# djshield2.net
KiCad netlist of a schematic drawn in EAGLE
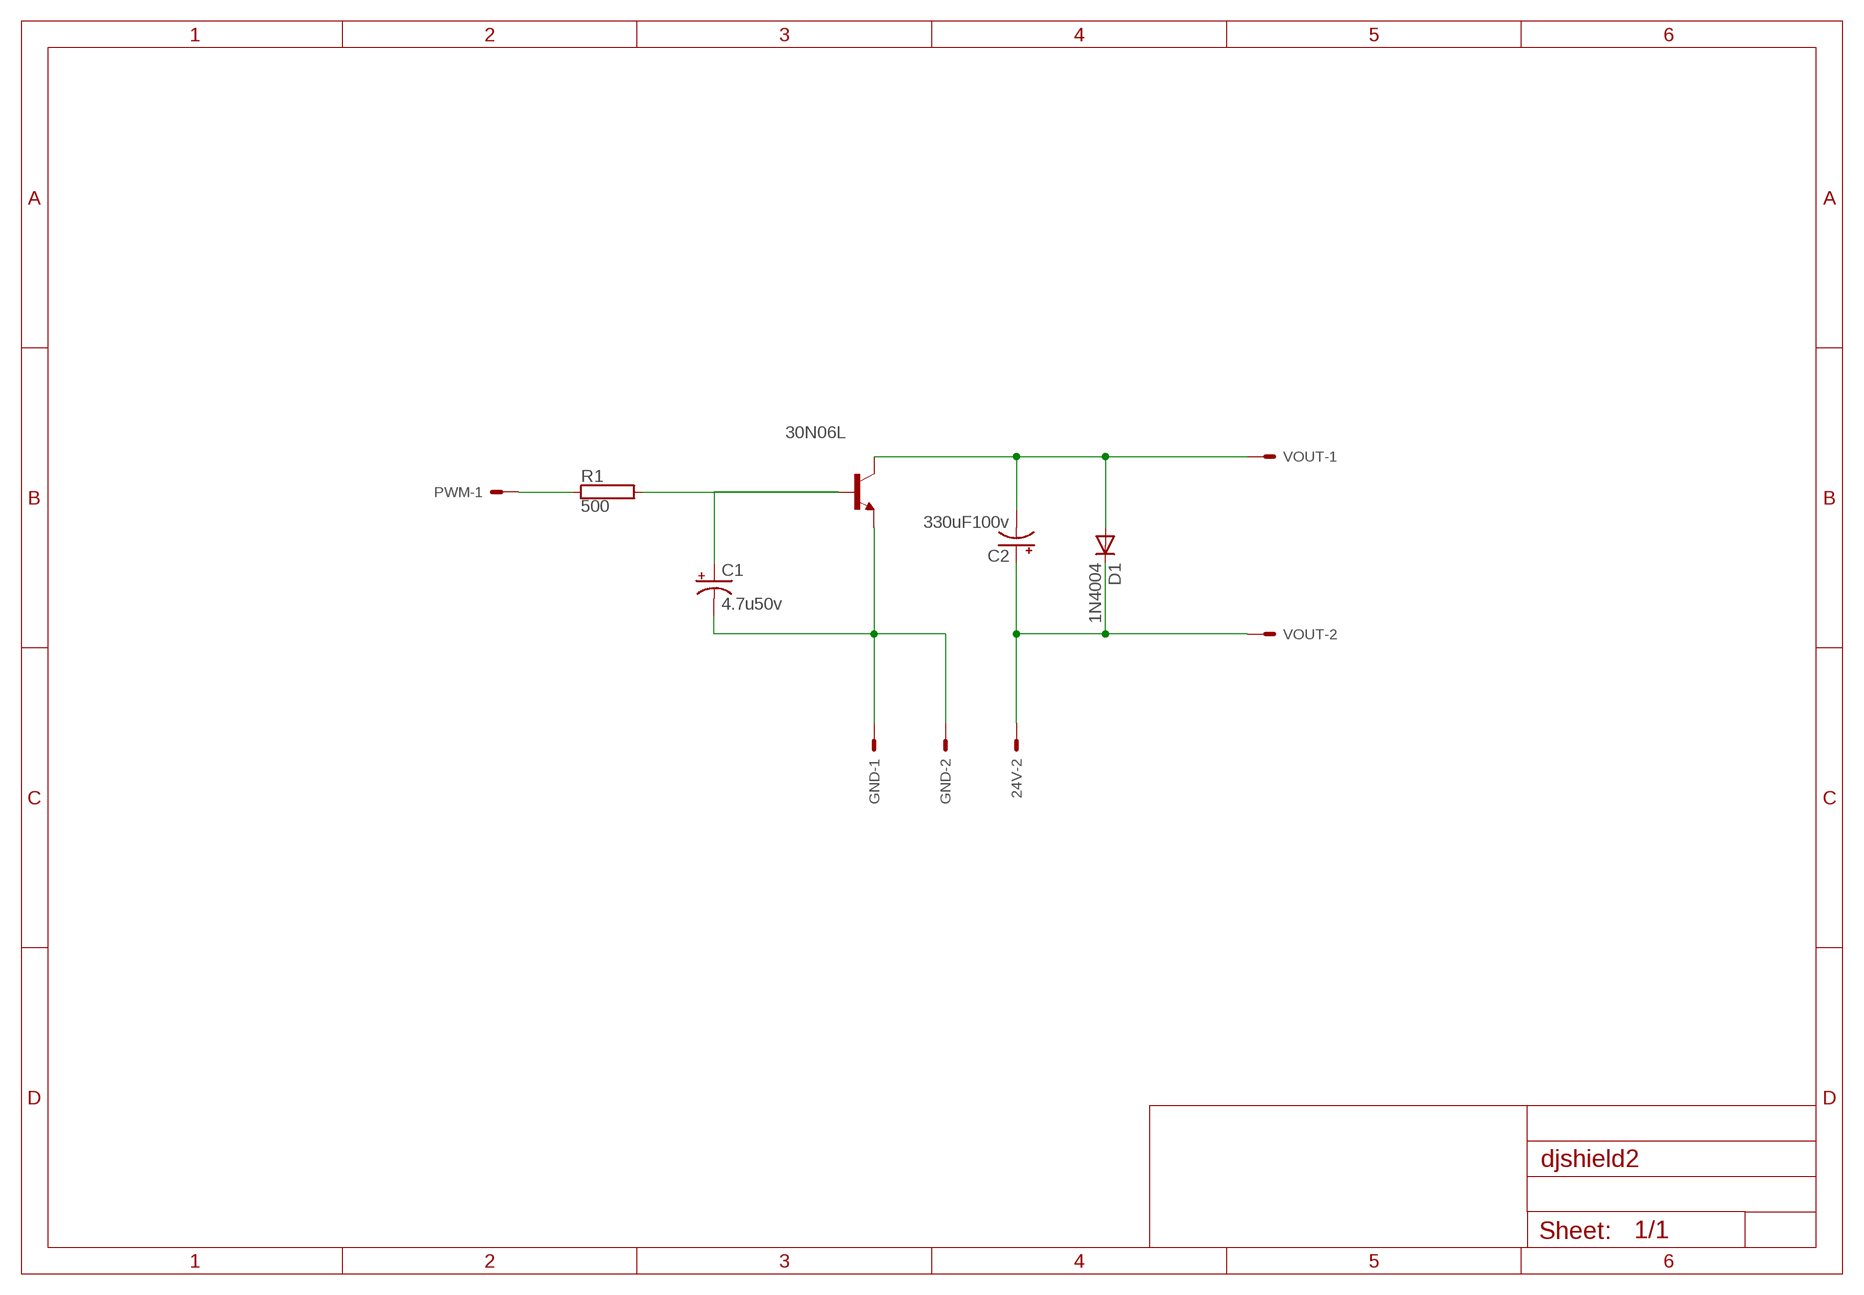
[diagram p0: schematic, sheet 1]

(export (version "E")
  (design (tool "Eeschema 10.0.6"))
  (components
    (comp (ref "24V")
      (value "87758-0216")
      (footprint "eagle-import:87758-0216")
      (libsource (lib "eagle-import") (part "87758-0216"))
    )
    (comp (ref "30N06L")
      (value "-NPN-TO126")
      (footprint "eagle-import:TO126")
      (libsource (lib "eagle-import") (part "-NPN-TO126"))
    )
    (comp (ref "C1")
      (value "4.7u50v")
      (footprint "eagle-import:E1,8-4")
      (libsource (lib "eagle-import") (part "resistor_CPOL-USE1.8-4"))
    )
    (comp (ref "C2")
      (value "330uF100v")
      (footprint "eagle-import:E35-18")
      (libsource (lib "eagle-import") (part "CPOL-USE35-18AXIAL"))
    )
    (comp (ref "D1")
      (value "1N4004")
      (footprint "eagle-import:DO41-10")
      (libsource (lib "eagle-import") (part "1N4004"))
    )
    (comp (ref "GND")
      (value "87758-0216")
      (footprint "eagle-import:87758-0216")
      (libsource (lib "eagle-import") (part "87758-0216"))
    )
    (comp (ref "PWM")
      (value "87758-0216")
      (footprint "eagle-import:87758-0216")
      (libsource (lib "eagle-import") (part "87758-0216"))
    )
    (comp (ref "R1")
      (value "500")
      (footprint "eagle-import:RS1_4")
      (fields (field (name "MF") "OHMITE") (field (name "MPN") "RRS1K0"))
      (libsource (lib "eagle-import") (part "RRS1/4"))
    )
    (comp (ref "VOUT")
      (value "87758-0216")
      (footprint "eagle-import:87758-0216")
      (libsource (lib "eagle-import") (part "87758-0216"))
    )
  )
  (nets
    (net (code "1") (name "Net-(24VB-S)") (class "Default")
      (node (ref "24V") (pin "2") (pinfunction "S_2") (pintype "passive"))
      (node (ref "C2") (pin "+") (pinfunction "+_+") (pintype "passive"))
      (node (ref "D1") (pin "C") (pinfunction "C_C") (pintype "passive"))
      (node (ref "VOUT") (pin "2") (pinfunction "S_2") (pintype "passive"))
    )
    (net (code "2") (name "Net-(30N06L-B)") (class "Default")
      (node (ref "30N06L") (pin "3") (pinfunction "B_3") (pintype "passive"))
      (node (ref "C1") (pin "+") (pinfunction "+_+") (pintype "passive"))
      (node (ref "R1") (pin "2") (pinfunction "2_2") (pintype "passive"))
    )
    (net (code "3") (name "Net-(30N06L-C)") (class "Default")
      (node (ref "30N06L") (pin "2") (pinfunction "C_2") (pintype "passive"))
      (node (ref "C2") (pin "-") (pinfunction "-_-") (pintype "passive"))
      (node (ref "D1") (pin "A") (pinfunction "A_A") (pintype "passive"))
      (node (ref "VOUT") (pin "1") (pinfunction "S_1") (pintype "passive"))
    )
    (net (code "4") (name "Net-(30N06L-E)") (class "Default")
      (node (ref "30N06L") (pin "1") (pinfunction "E_1") (pintype "passive"))
      (node (ref "C1") (pin "-") (pinfunction "-_-") (pintype "passive"))
      (node (ref "GND") (pin "1") (pinfunction "S_1") (pintype "passive"))
      (node (ref "GND") (pin "2") (pinfunction "S_2") (pintype "passive"))
    )
    (net (code "5") (name "Net-(PWMA-S)") (class "Default")
      (node (ref "PWM") (pin "1") (pinfunction "S_1") (pintype "passive"))
      (node (ref "R1") (pin "1") (pinfunction "1_1") (pintype "passive"))
    )
  )
)
